# 13thISE_ver8.net
KiCad netlist of a schematic drawn in EAGLE
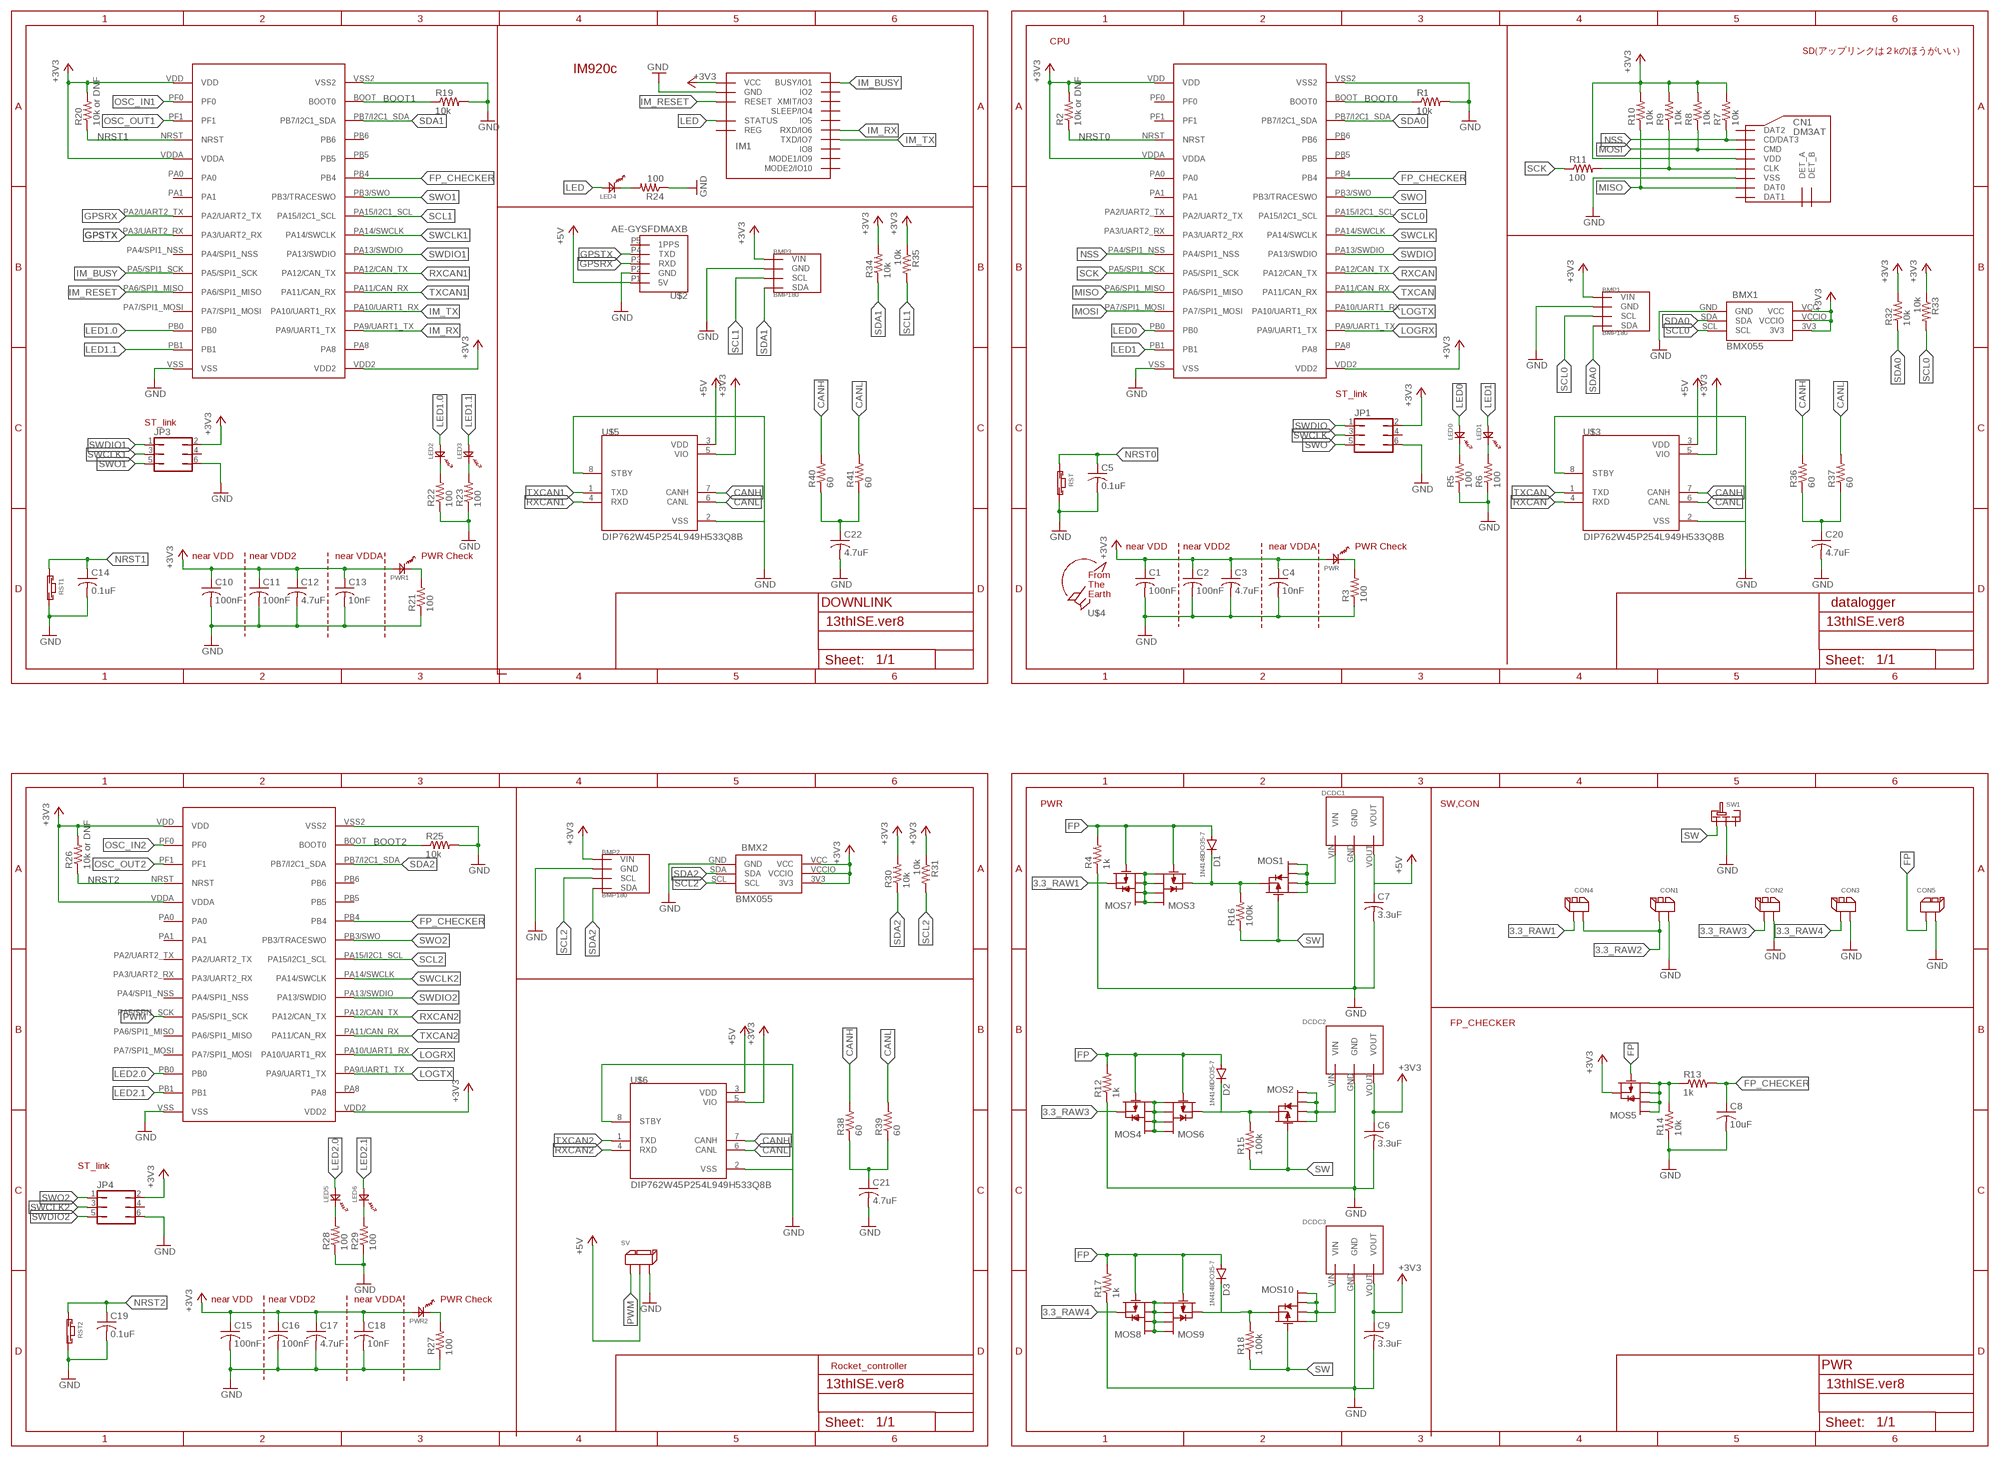
[diagram p0: schematic, sheet 1]

(export (version "E")
  (design (tool "Eeschema 10.0.6"))
  (components
    (comp (ref "BMP1")
      (value "BMP180")
      (footprint "eagle-import:GY-68")
      (libsource (lib "eagle-import") (part "BMP180"))
    )
    (comp (ref "BMP2")
      (value "BMP180")
      (footprint "eagle-import:GY-68")
      (libsource (lib "eagle-import") (part "BMP180"))
    )
    (comp (ref "BMP3")
      (value "BMP180")
      (footprint "eagle-import:GY-68")
      (libsource (lib "eagle-import") (part "BMP180"))
    )
    (comp (ref "BMX1")
      (value "BMX055")
      (footprint "eagle-import:BMX055")
      (libsource (lib "eagle-import") (part "BMX055"))
    )
    (comp (ref "BMX2")
      (value "BMX055")
      (footprint "eagle-import:BMX055")
      (libsource (lib "eagle-import") (part "BMX055"))
    )
    (comp (ref "C1")
      (value "100nF")
      (footprint "eagle-import:C1608")
      (libsource (lib "eagle-import") (part "C-USC1608"))
    )
    (comp (ref "C2")
      (value "100nF")
      (footprint "eagle-import:C1608")
      (libsource (lib "eagle-import") (part "C-USC1608"))
    )
    (comp (ref "C3")
      (value "4.7uF")
      (footprint "eagle-import:C1608")
      (libsource (lib "eagle-import") (part "C-USC1608"))
    )
    (comp (ref "C4")
      (value "10nF")
      (footprint "eagle-import:C1608")
      (libsource (lib "eagle-import") (part "C-USC1608"))
    )
    (comp (ref "C5")
      (value "0.1uF")
      (footprint "eagle-import:C1608")
      (libsource (lib "eagle-import") (part "C-USC1608"))
    )
    (comp (ref "C6")
      (value "3.3uF")
      (footprint "eagle-import:C0603")
      (libsource (lib "eagle-import") (part "C-USC0603"))
    )
    (comp (ref "C7")
      (value "3.3uF")
      (footprint "eagle-import:C0603")
      (libsource (lib "eagle-import") (part "C-USC0603"))
    )
    (comp (ref "C8")
      (value "10uF")
      (footprint "eagle-import:C0603")
      (libsource (lib "eagle-import") (part "C-USC0603"))
    )
    (comp (ref "C9")
      (value "3.3uF")
      (footprint "eagle-import:C0603")
      (libsource (lib "eagle-import") (part "C-USC0603"))
    )
    (comp (ref "C10")
      (value "100nF")
      (footprint "eagle-import:C1608")
      (libsource (lib "eagle-import") (part "C-USC1608"))
    )
    (comp (ref "C11")
      (value "100nF")
      (footprint "eagle-import:C1608")
      (libsource (lib "eagle-import") (part "C-USC1608"))
    )
    (comp (ref "C12")
      (value "4.7uF")
      (footprint "eagle-import:C1608")
      (libsource (lib "eagle-import") (part "C-USC1608"))
    )
    (comp (ref "C13")
      (value "10nF")
      (footprint "eagle-import:C1608")
      (libsource (lib "eagle-import") (part "C-USC1608"))
    )
    (comp (ref "C14")
      (value "0.1uF")
      (footprint "eagle-import:C1608")
      (libsource (lib "eagle-import") (part "C-USC1608"))
    )
    (comp (ref "C15")
      (value "100nF")
      (footprint "eagle-import:C1608")
      (libsource (lib "eagle-import") (part "C-USC1608"))
    )
    (comp (ref "C16")
      (value "100nF")
      (footprint "eagle-import:C1608")
      (libsource (lib "eagle-import") (part "C-USC1608"))
    )
    (comp (ref "C17")
      (value "4.7uF")
      (footprint "eagle-import:C1608")
      (libsource (lib "eagle-import") (part "C-USC1608"))
    )
    (comp (ref "C18")
      (value "10nF")
      (footprint "eagle-import:C1608")
      (libsource (lib "eagle-import") (part "C-USC1608"))
    )
    (comp (ref "C19")
      (value "0.1uF")
      (footprint "eagle-import:C1608")
      (libsource (lib "eagle-import") (part "C-USC1608"))
    )
    (comp (ref "C20")
      (value "4.7uF")
      (footprint "eagle-import:C0603")
      (libsource (lib "eagle-import") (part "C-USC0603"))
    )
    (comp (ref "C21")
      (value "4.7uF")
      (footprint "eagle-import:C0603")
      (libsource (lib "eagle-import") (part "C-USC0603"))
    )
    (comp (ref "C22")
      (value "4.7uF")
      (footprint "eagle-import:C0603")
      (libsource (lib "eagle-import") (part "C-USC0603"))
    )
    (comp (ref "CN1")
      (value "DM3AT")
      (footprint "eagle-import:DM3AT")
      (libsource (lib "eagle-import") (part "DM3AT"))
    )
    (comp (ref "CON1")
      (value "2PIN")
      (footprint "eagle-import:2PIN")
      (libsource (lib "eagle-import") (part "2PIN"))
    )
    (comp (ref "CON2")
      (value "2PIN")
      (footprint "eagle-import:2PIN")
      (libsource (lib "eagle-import") (part "2PIN"))
    )
    (comp (ref "CON3")
      (value "2PIN")
      (footprint "eagle-import:2PIN")
      (libsource (lib "eagle-import") (part "2PIN"))
    )
    (comp (ref "CON4")
      (value "2PIN")
      (footprint "eagle-import:2PIN")
      (libsource (lib "eagle-import") (part "2PIN"))
    )
    (comp (ref "CON5")
      (value "2PIN")
      (footprint "eagle-import:2PIN")
      (libsource (lib "eagle-import") (part "2PIN"))
    )
    (comp (ref "D1")
      (value "1N4148DO35-7")
      (footprint "eagle-import:DO35-7")
      (libsource (lib "eagle-import") (part "1N4148DO35-7"))
    )
    (comp (ref "D2")
      (value "1N4148DO35-7")
      (footprint "eagle-import:DO35-7")
      (libsource (lib "eagle-import") (part "1N4148DO35-7"))
    )
    (comp (ref "D3")
      (value "1N4148DO35-7")
      (footprint "eagle-import:DO35-7")
      (libsource (lib "eagle-import") (part "1N4148DO35-7"))
    )
    (comp (ref "DCDC1")
      (value "5V1A_M78AR05-1")
      (footprint "eagle-import:5V1A_M78AR05-1")
      (libsource (lib "eagle-import") (part "5V1A_M78AR05-1"))
    )
    (comp (ref "DCDC2")
      (value "3.3V1A_M78AR033-1")
      (footprint "eagle-import:3.3V1A_M78AR033-1")
      (libsource (lib "eagle-import") (part "3.3V1A_M78AR033-1"))
    )
    (comp (ref "DCDC3")
      (value "3.3V1A_M78AR033-1")
      (footprint "eagle-import:3.3V1A_M78AR033-1")
      (libsource (lib "eagle-import") (part "3.3V1A_M78AR033-1"))
    )
    (comp (ref "IM1")
      (value "IM920_IM920C")
      (footprint "eagle-import:IM920_IM920C")
      (libsource (lib "eagle-import") (part "IM920_IM920C"))
    )
    (comp (ref "JP1")
      (value "JP3Q")
      (footprint "eagle-import:JP3Q")
      (libsource (lib "eagle-import") (part "JP3Q"))
    )
    (comp (ref "JP3")
      (value "JP3Q")
      (footprint "eagle-import:JP3Q")
      (libsource (lib "eagle-import") (part "JP3Q"))
    )
    (comp (ref "JP4")
      (value "JP3Q")
      (footprint "eagle-import:JP3Q")
      (libsource (lib "eagle-import") (part "JP3Q"))
    )
    (comp (ref "LED0")
      (value "OSXX1608C1A")
      (footprint "eagle-import:OSXX1608C1A")
      (libsource (lib "eagle-import") (part "OSXX1608C1A"))
    )
    (comp (ref "LED1")
      (value "OSXX1608C1A")
      (footprint "eagle-import:OSXX1608C1A")
      (libsource (lib "eagle-import") (part "OSXX1608C1A"))
    )
    (comp (ref "LED2")
      (value "OSXX1608C1A")
      (footprint "eagle-import:OSXX1608C1A")
      (libsource (lib "eagle-import") (part "OSXX1608C1A"))
    )
    (comp (ref "LED3")
      (value "OSXX1608C1A")
      (footprint "eagle-import:OSXX1608C1A")
      (libsource (lib "eagle-import") (part "OSXX1608C1A"))
    )
    (comp (ref "LED4")
      (value "OSXX1608C1A")
      (footprint "eagle-import:OSXX1608C1A")
      (libsource (lib "eagle-import") (part "OSXX1608C1A"))
    )
    (comp (ref "LED5")
      (value "OSXX1608C1A")
      (footprint "eagle-import:OSXX1608C1A")
      (libsource (lib "eagle-import") (part "OSXX1608C1A"))
    )
    (comp (ref "LED6")
      (value "OSXX1608C1A")
      (footprint "eagle-import:OSXX1608C1A")
      (libsource (lib "eagle-import") (part "OSXX1608C1A"))
    )
    (comp (ref "MOS1")
      (value "PCH_SSM6J808R")
      (footprint "eagle-import:SSM6J808R")
      (libsource (lib "eagle-import") (part "PCH_SSM6J808R"))
    )
    (comp (ref "MOS2")
      (value "PCH_SSM6J808R")
      (footprint "eagle-import:SSM6J808R")
      (libsource (lib "eagle-import") (part "PCH_SSM6J808R"))
    )
    (comp (ref "MOS3")
      (value "PCH_SSM6J808R")
      (footprint "eagle-import:SSM6J808R")
      (libsource (lib "eagle-import") (part "PCH_SSM6J808R"))
    )
    (comp (ref "MOS4")
      (value "PCH_SSM6J808R")
      (footprint "eagle-import:SSM6J808R")
      (libsource (lib "eagle-import") (part "PCH_SSM6J808R"))
    )
    (comp (ref "MOS5")
      (value "PCH_SSM6J808R")
      (footprint "eagle-import:SSM6J808R")
      (libsource (lib "eagle-import") (part "PCH_SSM6J808R"))
    )
    (comp (ref "MOS6")
      (value "PCH_SSM6J808R")
      (footprint "eagle-import:SSM6J808R")
      (libsource (lib "eagle-import") (part "PCH_SSM6J808R"))
    )
    (comp (ref "MOS7")
      (value "PCH_SSM6J808R")
      (footprint "eagle-import:SSM6J808R")
      (libsource (lib "eagle-import") (part "PCH_SSM6J808R"))
    )
    (comp (ref "MOS8")
      (value "PCH_SSM6J808R")
      (footprint "eagle-import:SSM6J808R")
      (libsource (lib "eagle-import") (part "PCH_SSM6J808R"))
    )
    (comp (ref "MOS9")
      (value "PCH_SSM6J808R")
      (footprint "eagle-import:SSM6J808R")
      (libsource (lib "eagle-import") (part "PCH_SSM6J808R"))
    )
    (comp (ref "MOS10")
      (value "PCH_SSM6J808R")
      (footprint "eagle-import:SSM6J808R")
      (libsource (lib "eagle-import") (part "PCH_SSM6J808R"))
    )
    (comp (ref "PWR")
      (value "OSXX1608C1A")
      (footprint "eagle-import:OSXX1608C1A")
      (libsource (lib "eagle-import") (part "OSXX1608C1A"))
    )
    (comp (ref "PWR1")
      (value "OSXX1608C1A")
      (footprint "eagle-import:OSXX1608C1A")
      (libsource (lib "eagle-import") (part "OSXX1608C1A"))
    )
    (comp (ref "PWR2")
      (value "OSXX1608C1A")
      (footprint "eagle-import:OSXX1608C1A")
      (libsource (lib "eagle-import") (part "OSXX1608C1A"))
    )
    (comp (ref "R1")
      (value "10k")
      (footprint "eagle-import:R0603")
      (libsource (lib "eagle-import") (part "R-US_R0603"))
    )
    (comp (ref "R2")
      (value "10k or DNF")
      (footprint "eagle-import:R0603")
      (libsource (lib "eagle-import") (part "R-US_R0603"))
    )
    (comp (ref "R3")
      (value "100")
      (footprint "eagle-import:R0603")
      (libsource (lib "eagle-import") (part "R-US_R0603"))
    )
    (comp (ref "R4")
      (value "1k")
      (footprint "eagle-import:R0603")
      (libsource (lib "eagle-import") (part "R-US_R0603"))
    )
    (comp (ref "R5")
      (value "100")
      (footprint "eagle-import:R0603")
      (libsource (lib "eagle-import") (part "R-US_R0603"))
    )
    (comp (ref "R6")
      (value "100")
      (footprint "eagle-import:R0603")
      (libsource (lib "eagle-import") (part "R-US_R0603"))
    )
    (comp (ref "R7")
      (value "10k")
      (footprint "eagle-import:R0603")
      (libsource (lib "eagle-import") (part "R-US_R0603"))
    )
    (comp (ref "R8")
      (value "10k")
      (footprint "eagle-import:R0603")
      (libsource (lib "eagle-import") (part "R-US_R0603"))
    )
    (comp (ref "R9")
      (value "10k")
      (footprint "eagle-import:R0603")
      (libsource (lib "eagle-import") (part "R-US_R0603"))
    )
    (comp (ref "R10")
      (value "10k")
      (footprint "eagle-import:R0603")
      (libsource (lib "eagle-import") (part "R-US_R0603"))
    )
    (comp (ref "R11")
      (value "100")
      (footprint "eagle-import:R0603")
      (libsource (lib "eagle-import") (part "R-US_R0603"))
    )
    (comp (ref "R12")
      (value "1k")
      (footprint "eagle-import:R0603")
      (libsource (lib "eagle-import") (part "R-US_R0603"))
    )
    (comp (ref "R13")
      (value "1k")
      (footprint "eagle-import:R0603")
      (libsource (lib "eagle-import") (part "R-US_R0603"))
    )
    (comp (ref "R14")
      (value "10k")
      (footprint "eagle-import:R0603")
      (libsource (lib "eagle-import") (part "R-US_R0603"))
    )
    (comp (ref "R15")
      (value "100k")
      (footprint "eagle-import:R0603")
      (libsource (lib "eagle-import") (part "R-US_R0603"))
    )
    (comp (ref "R16")
      (value "100k")
      (footprint "eagle-import:R0603")
      (libsource (lib "eagle-import") (part "R-US_R0603"))
    )
    (comp (ref "R17")
      (value "1k")
      (footprint "eagle-import:R0603")
      (libsource (lib "eagle-import") (part "R-US_R0603"))
    )
    (comp (ref "R18")
      (value "100k")
      (footprint "eagle-import:R0603")
      (libsource (lib "eagle-import") (part "R-US_R0603"))
    )
    (comp (ref "R19")
      (value "10k")
      (footprint "eagle-import:R0603")
      (libsource (lib "eagle-import") (part "R-US_R0603"))
    )
    (comp (ref "R20")
      (value "10k or DNF")
      (footprint "eagle-import:R0603")
      (libsource (lib "eagle-import") (part "R-US_R0603"))
    )
    (comp (ref "R21")
      (value "100")
      (footprint "eagle-import:R0603")
      (libsource (lib "eagle-import") (part "R-US_R0603"))
    )
    (comp (ref "R22")
      (value "100")
      (footprint "eagle-import:R0603")
      (libsource (lib "eagle-import") (part "R-US_R0603"))
    )
    (comp (ref "R23")
      (value "100")
      (footprint "eagle-import:R0603")
      (libsource (lib "eagle-import") (part "R-US_R0603"))
    )
    (comp (ref "R24")
      (value "100")
      (footprint "eagle-import:R0603")
      (libsource (lib "eagle-import") (part "R-US_R0603"))
    )
    (comp (ref "R25")
      (value "10k")
      (footprint "eagle-import:R0603")
      (libsource (lib "eagle-import") (part "R-US_R0603"))
    )
    (comp (ref "R26")
      (value "10k or DNF")
      (footprint "eagle-import:R0603")
      (libsource (lib "eagle-import") (part "R-US_R0603"))
    )
    (comp (ref "R27")
      (value "100")
      (footprint "eagle-import:R0603")
      (libsource (lib "eagle-import") (part "R-US_R0603"))
    )
    (comp (ref "R28")
      (value "100")
      (footprint "eagle-import:R0603")
      (libsource (lib "eagle-import") (part "R-US_R0603"))
    )
    (comp (ref "R29")
      (value "100")
      (footprint "eagle-import:R0603")
      (libsource (lib "eagle-import") (part "R-US_R0603"))
    )
    (comp (ref "R30")
      (value "10k")
      (footprint "eagle-import:R0603")
      (libsource (lib "eagle-import") (part "R-US_R0603"))
    )
    (comp (ref "R31")
      (value "10k")
      (footprint "eagle-import:R0603")
      (libsource (lib "eagle-import") (part "R-US_R0603"))
    )
    (comp (ref "R32")
      (value "10k")
      (footprint "eagle-import:R0603")
      (libsource (lib "eagle-import") (part "R-US_R0603"))
    )
    (comp (ref "R33")
      (value "10k")
      (footprint "eagle-import:R0603")
      (libsource (lib "eagle-import") (part "R-US_R0603"))
    )
    (comp (ref "R34")
      (value "10k")
      (footprint "eagle-import:R0603")
      (libsource (lib "eagle-import") (part "R-US_R0603"))
    )
    (comp (ref "R35")
      (value "10k")
      (footprint "eagle-import:R0603")
      (libsource (lib "eagle-import") (part "R-US_R0603"))
    )
    (comp (ref "R36")
      (value "60")
      (footprint "eagle-import:R0603")
      (libsource (lib "eagle-import") (part "R-US_R0603"))
    )
    (comp (ref "R37")
      (value "60")
      (footprint "eagle-import:R0603")
      (libsource (lib "eagle-import") (part "R-US_R0603"))
    )
    (comp (ref "R38")
      (value "60")
      (footprint "eagle-import:R0603")
      (libsource (lib "eagle-import") (part "R-US_R0603"))
    )
    (comp (ref "R39")
      (value "60")
      (footprint "eagle-import:R0603")
      (libsource (lib "eagle-import") (part "R-US_R0603"))
    )
    (comp (ref "R40")
      (value "60")
      (footprint "eagle-import:R0603")
      (libsource (lib "eagle-import") (part "R-US_R0603"))
    )
    (comp (ref "R41")
      (value "60")
      (footprint "eagle-import:R0603")
      (libsource (lib "eagle-import") (part "R-US_R0603"))
    )
    (comp (ref "RST")
      (value "TVAF06-A020B-R")
      (footprint "eagle-import:TVAF06-A020B-R")
      (libsource (lib "eagle-import") (part "TVAF06-A020B-R"))
    )
    (comp (ref "RST1")
      (value "TVAF06-A020B-R")
      (footprint "eagle-import:TVAF06-A020B-R")
      (libsource (lib "eagle-import") (part "TVAF06-A020B-R"))
    )
    (comp (ref "RST2")
      (value "TVAF06-A020B-R")
      (footprint "eagle-import:TVAF06-A020B-R")
      (libsource (lib "eagle-import") (part "TVAF06-A020B-R"))
    )
    (comp (ref "STM0")
      (value "STM32F303K8")
      (footprint "eagle-import:STM32F303K8")
      (libsource (lib "eagle-import") (part "STM32F303K8"))
    )
    (comp (ref "STM1")
      (value "STM32F303K8")
      (footprint "eagle-import:STM32F303K8")
      (libsource (lib "eagle-import") (part "STM32F303K8"))
    )
    (comp (ref "SV")
      (value "3PIN")
      (footprint "eagle-import:3PIN")
      (libsource (lib "eagle-import") (part "3PIN"))
    )
    (comp (ref "SW1")
      (value "SRIDE_SWITCH")
      (footprint "eagle-import:SRIDE_SWITCH")
      (libsource (lib "eagle-import") (part "SRIDE_SWITCH"))
    )
    (comp (ref "U$1")
      (value "STM32F303K8")
      (footprint "eagle-import:STM32F303K8")
      (libsource (lib "eagle-import") (part "STM32F303K8"))
    )
    (comp (ref "U$2")
      (value "AE-GYSFDMAXB")
      (footprint "eagle-import:AE-GYSFDMAXB")
      (libsource (lib "eagle-import") (part "AE-GYSFDMAXB"))
    )
    (comp (ref "U$3")
      (value "DIP762W45P254L949H533Q8B")
      (footprint "eagle-import:DIP762W45P254L949H533Q8B")
      (libsource (lib "eagle-import") (part "DIP762W45P254L949H533Q8B"))
    )
    (comp (ref "U$4")
      (value "F.T.E.LOGO")
      (footprint "eagle-import:LOGO")
      (libsource (lib "eagle-import") (part "F.T.E.LOGO"))
    )
    (comp (ref "U$5")
      (value "DIP762W45P254L949H533Q8B")
      (footprint "eagle-import:DIP762W45P254L949H533Q8B")
      (libsource (lib "eagle-import") (part "DIP762W45P254L949H533Q8B"))
    )
    (comp (ref "U$6")
      (value "DIP762W45P254L949H533Q8B")
      (footprint "eagle-import:DIP762W45P254L949H533Q8B")
      (libsource (lib "eagle-import") (part "DIP762W45P254L949H533Q8B"))
    )
  )
  (nets
    (net (code "1") (name "+3V3") (class "Default")
      (node (ref "BMP1") (pin "P1") (pinfunction "VIN_P1") (pintype "bidirectional"))
      (node (ref "BMP2") (pin "P1") (pinfunction "VIN_P1") (pintype "bidirectional"))
      (node (ref "BMP3") (pin "P1") (pinfunction "VIN_P1") (pintype "bidirectional"))
      (node (ref "BMX1") (pin "3V3") (pinfunction "3V3_3V3") (pintype "power_in"))
      (node (ref "BMX1") (pin "VCC") (pinfunction "VCC_VCC") (pintype "power_in"))
      (node (ref "BMX1") (pin "VCCIO") (pinfunction "VCCIO_VCCIO") (pintype "power_in"))
      (node (ref "BMX2") (pin "3V3") (pinfunction "3V3_3V3") (pintype "power_in"))
      (node (ref "BMX2") (pin "VCC") (pinfunction "VCC_VCC") (pintype "power_in"))
      (node (ref "BMX2") (pin "VCCIO") (pinfunction "VCCIO_VCCIO") (pintype "power_in"))
      (node (ref "C1") (pin "1") (pinfunction "1_1") (pintype "passive"))
      (node (ref "C10") (pin "1") (pinfunction "1_1") (pintype "passive"))
      (node (ref "C11") (pin "1") (pinfunction "1_1") (pintype "passive"))
      (node (ref "C12") (pin "1") (pinfunction "1_1") (pintype "passive"))
      (node (ref "C13") (pin "1") (pinfunction "1_1") (pintype "passive"))
      (node (ref "C15") (pin "1") (pinfunction "1_1") (pintype "passive"))
      (node (ref "C16") (pin "1") (pinfunction "1_1") (pintype "passive"))
      (node (ref "C17") (pin "1") (pinfunction "1_1") (pintype "passive"))
      (node (ref "C18") (pin "1") (pinfunction "1_1") (pintype "passive"))
      (node (ref "C2") (pin "1") (pinfunction "1_1") (pintype "passive"))
      (node (ref "C3") (pin "1") (pinfunction "1_1") (pintype "passive"))
      (node (ref "C4") (pin "1") (pinfunction "1_1") (pintype "passive"))
      (node (ref "C6") (pin "1") (pinfunction "1_1") (pintype "passive"))
      (node (ref "C9") (pin "1") (pinfunction "1_1") (pintype "passive"))
      (node (ref "CN1") (pin "VDD") (pinfunction "VDD_VDD") (pintype "bidirectional"))
      (node (ref "DCDC2") (pin "VOUT") (pinfunction "VOUT_VOUT") (pintype "bidirectional"))
      (node (ref "DCDC3") (pin "VOUT") (pinfunction "VOUT_VOUT") (pintype "bidirectional"))
      (node (ref "IM1") (pin "$P17") (pinfunction "VCC_$P17") (pintype "bidirectional"))
      (node (ref "JP1") (pin "2") (pinfunction "2_2") (pintype "passive"))
      (node (ref "JP3") (pin "2") (pinfunction "2_2") (pintype "passive"))
      (node (ref "JP4") (pin "2") (pinfunction "2_2") (pintype "passive"))
      (node (ref "MOS5") (pin "4") (pinfunction "4_4") (pintype "bidirectional"))
      (node (ref "PWR") (pin "AN") (pinfunction "AN_AN") (pintype "bidirectional"))
      (node (ref "PWR1") (pin "AN") (pinfunction "AN_AN") (pintype "bidirectional"))
      (node (ref "PWR2") (pin "AN") (pinfunction "AN_AN") (pintype "bidirectional"))
      (node (ref "R10") (pin "2") (pinfunction "2_2") (pintype "passive"))
      (node (ref "R2") (pin "2") (pinfunction "2_2") (pintype "passive"))
      (node (ref "R20") (pin "2") (pinfunction "2_2") (pintype "passive"))
      (node (ref "R26") (pin "2") (pinfunction "2_2") (pintype "passive"))
      (node (ref "R30") (pin "2") (pinfunction "2_2") (pintype "passive"))
      (node (ref "R31") (pin "1") (pinfunction "1_1") (pintype "passive"))
      (node (ref "R32") (pin "2") (pinfunction "2_2") (pintype "passive"))
      (node (ref "R33") (pin "1") (pinfunction "1_1") (pintype "passive"))
      (node (ref "R34") (pin "2") (pinfunction "2_2") (pintype "passive"))
      (node (ref "R35") (pin "1") (pinfunction "1_1") (pintype "passive"))
      (node (ref "R7") (pin "2") (pinfunction "2_2") (pintype "passive"))
      (node (ref "R8") (pin "2") (pinfunction "2_2") (pintype "passive"))
      (node (ref "R9") (pin "2") (pinfunction "2_2") (pintype "passive"))
      (node (ref "STM0") (pin "VDD") (pinfunction "VDD_VDD") (pintype "power_in"))
      (node (ref "STM0") (pin "VDD2") (pinfunction "VDD2_VDD2") (pintype "power_in"))
      (node (ref "STM0") (pin "VDDA") (pinfunction "VDDA_VDDA") (pintype "power_in"))
      (node (ref "STM1") (pin "VDD") (pinfunction "VDD_VDD") (pintype "power_in"))
      (node (ref "STM1") (pin "VDD2") (pinfunction "VDD2_VDD2") (pintype "power_in"))
      (node (ref "STM1") (pin "VDDA") (pinfunction "VDDA_VDDA") (pintype "power_in"))
      (node (ref "U$1") (pin "VDD") (pinfunction "VDD_VDD") (pintype "power_in"))
      (node (ref "U$1") (pin "VDD2") (pinfunction "VDD2_VDD2") (pintype "power_in"))
      (node (ref "U$1") (pin "VDDA") (pinfunction "VDDA_VDDA") (pintype "power_in"))
      (node (ref "U$3") (pin "5") (pinfunction "VIO_5") (pintype "power_in"))
      (node (ref "U$5") (pin "5") (pinfunction "VIO_5") (pintype "power_in"))
      (node (ref "U$6") (pin "5") (pinfunction "VIO_5") (pintype "power_in"))
    )
    (net (code "2") (name "+5V") (class "Default")
      (node (ref "C7") (pin "1") (pinfunction "1_1") (pintype "passive"))
      (node (ref "DCDC1") (pin "VOUT") (pinfunction "VOUT_VOUT") (pintype "bidirectional"))
      (node (ref "SV") (pin "P$2") (pinfunction "P$2_P$2") (pintype "bidirectional"))
      (node (ref "U$2") (pin "P1") (pinfunction "5V_P1") (pintype "bidirectional"))
      (node (ref "U$3") (pin "3") (pinfunction "VDD_3") (pintype "power_in"))
      (node (ref "U$5") (pin "3") (pinfunction "VDD_3") (pintype "power_in"))
      (node (ref "U$6") (pin "3") (pinfunction "VDD_3") (pintype "power_in"))
    )
    (net (code "3") (name "/BOOT0") (class "Default")
      (node (ref "R1") (pin "1") (pinfunction "1_1") (pintype "passive"))
      (node (ref "STM0") (pin "BOOT") (pinfunction "BOOT0_BOOT") (pintype "bidirectional"))
    )
    (net (code "4") (name "/BOOT1") (class "Default")
      (node (ref "R19") (pin "1") (pinfunction "1_1") (pintype "passive"))
      (node (ref "STM1") (pin "BOOT") (pinfunction "BOOT0_BOOT") (pintype "bidirectional"))
    )
    (net (code "5") (name "/BOOT2") (class "Default")
      (node (ref "R25") (pin "1") (pinfunction "1_1") (pintype "passive"))
      (node (ref "U$1") (pin "BOOT") (pinfunction "BOOT0_BOOT") (pintype "bidirectional"))
    )
    (net (code "6") (name "3.3_RAW1") (class "Default")
      (node (ref "CON4") (pin "P$2") (pinfunction "P$2_P$2") (pintype "bidirectional"))
      (node (ref "MOS7") (pin "4") (pinfunction "4_4") (pintype "bidirectional"))
    )
    (net (code "7") (name "3.3_RAW2") (class "Default")
      (node (ref "CON1") (pin "P$2") (pinfunction "P$2_P$2") (pintype "bidirectional"))
      (node (ref "CON4") (pin "P$1") (pinfunction "P$1_P$1") (pintype "bidirectional"))
    )
    (net (code "8") (name "3.3_RAW3") (class "Default")
      (node (ref "CON2") (pin "P$2") (pinfunction "P$2_P$2") (pintype "bidirectional"))
      (node (ref "MOS4") (pin "4") (pinfunction "4_4") (pintype "bidirectional"))
    )
    (net (code "9") (name "3.3_RAW4") (class "Default")
      (node (ref "CON3") (pin "P$2") (pinfunction "P$2_P$2") (pintype "bidirectional"))
      (node (ref "MOS8") (pin "4") (pinfunction "4_4") (pintype "bidirectional"))
    )
    (net (code "10") (name "CANH") (class "Default")
      (node (ref "R36") (pin "2") (pinfunction "2_2") (pintype "passive"))
      (node (ref "R38") (pin "2") (pinfunction "2_2") (pintype "passive"))
      (node (ref "R40") (pin "2") (pinfunction "2_2") (pintype "passive"))
      (node (ref "U$3") (pin "7") (pinfunction "CANH_7") (pintype "bidirectional"))
      (node (ref "U$5") (pin "7") (pinfunction "CANH_7") (pintype "bidirectional"))
      (node (ref "U$6") (pin "7") (pinfunction "CANH_7") (pintype "bidirectional"))
    )
    (net (code "11") (name "CANL") (class "Default")
      (node (ref "R37") (pin "2") (pinfunction "2_2") (pintype "passive"))
      (node (ref "R39") (pin "2") (pinfunction "2_2") (pintype "passive"))
      (node (ref "R41") (pin "2") (pinfunction "2_2") (pintype "passive"))
      (node (ref "U$3") (pin "6") (pinfunction "CANL_6") (pintype "bidirectional"))
      (node (ref "U$5") (pin "6") (pinfunction "CANL_6") (pintype "bidirectional"))
      (node (ref "U$6") (pin "6") (pinfunction "CANL_6") (pintype "bidirectional"))
    )
    (net (code "12") (name "FP") (class "Default")
      (node (ref "CON5") (pin "P$1") (pinfunction "P$1_P$1") (pintype "bidirectional"))
      (node (ref "D1") (pin "A") (pinfunction "A_A") (pintype "passive"))
      (node (ref "D2") (pin "A") (pinfunction "A_A") (pintype "passive"))
      (node (ref "D3") (pin "A") (pinfunction "A_A") (pintype "passive"))
      (node (ref "MOS3") (pin "3") (pinfunction "3_3") (pintype "bidirectional"))
      (node (ref "MOS4") (pin "3") (pinfunction "3_3") (pintype "bidirectional"))
      (node (ref "MOS5") (pin "3") (pinfunction "3_3") (pintype "bidirectional"))
      (node (ref "MOS6") (pin "3") (pinfunction "3_3") (pintype "bidirectional"))
      (node (ref "MOS7") (pin "3") (pinfunction "3_3") (pintype "bidirectional"))
      (node (ref "MOS8") (pin "3") (pinfunction "3_3") (pintype "bidirectional"))
      (node (ref "MOS9") (pin "3") (pinfunction "3_3") (pintype "bidirectional"))
      (node (ref "R12") (pin "2") (pinfunction "2_2") (pintype "passive"))
      (node (ref "R17") (pin "2") (pinfunction "2_2") (pintype "passive"))
      (node (ref "R4") (pin "2") (pinfunction "2_2") (pintype "passive"))
    )
    (net (code "13") (name "FP_CHECKER") (class "Default")
      (node (ref "C8") (pin "1") (pinfunction "1_1") (pintype "passive"))
      (node (ref "R13") (pin "2") (pinfunction "2_2") (pintype "passive"))
      (node (ref "STM0") (pin "PB4") (pinfunction "PB4_PB4") (pintype "bidirectional"))
      (node (ref "STM1") (pin "PB4") (pinfunction "PB4_PB4") (pintype "bidirectional"))
      (node (ref "U$1") (pin "PB4") (pinfunction "PB4_PB4") (pintype "bidirectional"))
    )
    (net (code "14") (name "GND") (class "Default")
      (node (ref "BMP1") (pin "P2") (pinfunction "GND_P2") (pintype "bidirectional"))
      (node (ref "BMP2") (pin "P2") (pinfunction "GND_P2") (pintype "bidirectional"))
      (node (ref "BMP3") (pin "P2") (pinfunction "GND_P2") (pintype "bidirectional"))
      (node (ref "BMX1") (pin "GND") (pinfunction "GND_GND") (pintype "power_in"))
      (node (ref "BMX2") (pin "GND") (pinfunction "GND_GND") (pintype "power_in"))
      (node (ref "C1") (pin "2") (pinfunction "2_2") (pintype "passive"))
      (node (ref "C10") (pin "2") (pinfunction "2_2") (pintype "passive"))
      (node (ref "C11") (pin "2") (pinfunction "2_2") (pintype "passive"))
      (node (ref "C12") (pin "2") (pinfunction "2_2") (pintype "passive"))
      (node (ref "C13") (pin "2") (pinfunction "2_2") (pintype "passive"))
      (node (ref "C14") (pin "2") (pinfunction "2_2") (pintype "passive"))
      (node (ref "C15") (pin "2") (pinfunction "2_2") (pintype "passive"))
      (node (ref "C16") (pin "2") (pinfunction "2_2") (pintype "passive"))
      (node (ref "C17") (pin "2") (pinfunction "2_2") (pintype "passive"))
      (node (ref "C18") (pin "2") (pinfunction "2_2") (pintype "passive"))
      (node (ref "C19") (pin "2") (pinfunction "2_2") (pintype "passive"))
      (node (ref "C2") (pin "2") (pinfunction "2_2") (pintype "passive"))
      (node (ref "C20") (pin "2") (pinfunction "2_2") (pintype "passive"))
      (node (ref "C21") (pin "2") (pinfunction "2_2") (pintype "passive"))
      (node (ref "C22") (pin "2") (pinfunction "2_2") (pintype "passive"))
      (node (ref "C3") (pin "2") (pinfunction "2_2") (pintype "passive"))
      (node (ref "C4") (pin "2") (pinfunction "2_2") (pintype "passive"))
      (node (ref "C5") (pin "2") (pinfunction "2_2") (pintype "passive"))
      (node (ref "C6") (pin "2") (pinfunction "2_2") (pintype "passive"))
      (node (ref "C7") (pin "2") (pinfunction "2_2") (pintype "passive"))
      (node (ref "C8") (pin "2") (pinfunction "2_2") (pintype "passive"))
      (node (ref "C9") (pin "2") (pinfunction "2_2") (pintype "passive"))
      (node (ref "CN1") (pin "VSS") (pinfunction "VSS_VSS") (pintype "bidirectional"))
      (node (ref "CON1") (pin "P$1") (pinfunction "P$1_P$1") (pintype "bidirectional"))
      (node (ref "CON2") (pin "P$1") (pinfunction "P$1_P$1") (pintype "bidirectional"))
      (node (ref "CON3") (pin "P$1") (pinfunction "P$1_P$1") (pintype "bidirectional"))
      (node (ref "CON5") (pin "P$2") (pinfunction "P$2_P$2") (pintype "bidirectional"))
      (node (ref "DCDC1") (pin "GND") (pinfunction "GND_GND") (pintype "bidirectional"))
      (node (ref "DCDC2") (pin "GND") (pinfunction "GND_GND") (pintype "bidirectional"))
      (node (ref "DCDC3") (pin "GND") (pinfunction "GND_GND") (pintype "bidirectional"))
      (node (ref "IM1") (pin "$P18") (pinfunction "GND_$P18") (pintype "bidirectional"))
      (node (ref "JP1") (pin "6") (pinfunction "6_6") (pintype "passive"))
      (node (ref "JP3") (pin "6") (pinfunction "6_6") (pintype "passive"))
      (node (ref "JP4") (pin "6") (pinfunction "6_6") (pintype "passive"))
      (node (ref "R1") (pin "2") (pinfunction "2_2") (pintype "passive"))
      (node (ref "R12") (pin "1") (pinfunction "1_1") (pintype "passive"))
      (node (ref "R14") (pin "1") (pinfunction "1_1") (pintype "passive"))
      (node (ref "R17") (pin "1") (pinfunction "1_1") (pintype "passive"))
      (node (ref "R19") (pin "2") (pinfunction "2_2") (pintype "passive"))
      (node (ref "R21") (pin "1") (pinfunction "1_1") (pintype "passive"))
      (node (ref "R22") (pin "1") (pinfunction "1_1") (pintype "passive"))
      (node (ref "R23") (pin "1") (pinfunction "1_1") (pintype "passive"))
      (node (ref "R24") (pin "1") (pinfunction "1_1") (pintype "passive"))
      (node (ref "R25") (pin "2") (pinfunction "2_2") (pintype "passive"))
      (node (ref "R27") (pin "1") (pinfunction "1_1") (pintype "passive"))
      (node (ref "R28") (pin "1") (pinfunction "1_1") (pintype "passive"))
      (node (ref "R29") (pin "1") (pinfunction "1_1") (pintype "passive"))
      (node (ref "R3") (pin "1") (pinfunction "1_1") (pintype "passive"))
      (node (ref "R4") (pin "1") (pinfunction "1_1") (pintype "passive"))
      (node (ref "R5") (pin "1") (pinfunction "1_1") (pintype "passive"))
      (node (ref "R6") (pin "1") (pinfunction "1_1") (pintype "passive"))
      (node (ref "RST") (pin "P$2") (pinfunction "P$2_P$2") (pintype "bidirectional"))
      (node (ref "RST1") (pin "P$2") (pinfunction "P$2_P$2") (pintype "bidirectional"))
      (node (ref "RST2") (pin "P$2") (pinfunction "P$2_P$2") (pintype "bidirectional"))
      (node (ref "STM0") (pin "VSS") (pinfunction "VSS_VSS") (pintype "power_in"))
      (node (ref "STM0") (pin "VSS2") (pinfunction "VSS2_VSS2") (pintype "power_in"))
      (node (ref "STM1") (pin "VSS") (pinfunction "VSS_VSS") (pintype "power_in"))
      (node (ref "STM1") (pin "VSS2") (pinfunction "VSS2_VSS2") (pintype "power_in"))
      (node (ref "SV") (pin "P$3") (pinfunction "P$3_P$3") (pintype "bidirectional"))
      (node (ref "SW1") (pin "LR") (pinfunction "LR_LR") (pintype "bidirectional"))
      (node (ref "U$1") (pin "VSS") (pinfunction "VSS_VSS") (pintype "power_in"))
      (node (ref "U$1") (pin "VSS2") (pinfunction "VSS2_VSS2") (pintype "power_in"))
      (node (ref "U$2") (pin "P2") (pinfunction "GND_P2") (pintype "bidirectional"))
      (node (ref "U$3") (pin "2") (pinfunction "VSS_2") (pintype "power_in"))
      (node (ref "U$3") (pin "8") (pinfunction "STBY_8") (pintype "input"))
      (node (ref "U$5") (pin "2") (pinfunction "VSS_2") (pintype "power_in"))
      (node (ref "U$5") (pin "8") (pinfunction "STBY_8") (pintype "input"))
      (node (ref "U$6") (pin "2") (pinfunction "VSS_2") (pintype "power_in"))
      (node (ref "U$6") (pin "8") (pinfunction "STBY_8") (pintype "input"))
    )
    (net (code "15") (name "GPSRX") (class "Default")
      (node (ref "STM1") (pin "PA2/UART2_TX") (pinfunction "PA2/UART2_TX_PA2/UART2_TX") (pintype "bidirectional"))
      (node (ref "U$2") (pin "P3") (pinfunction "RXD_P3") (pintype "bidirectional"))
    )
    (net (code "16") (name "GPSTX") (class "Default")
      (node (ref "STM1") (pin "PA3/UART2_RX") (pinfunction "PA3/UART2_RX_PA3/UART2_RX") (pintype "bidirectional"))
      (node (ref "U$2") (pin "P4") (pinfunction "TXD_P4") (pintype "bidirectional"))
    )
    (net (code "17") (name "IM_BUSY") (class "Default")
      (node (ref "IM1") (pin "$P1") (pinfunction "BUSY/IO1_$P1") (pintype "bidirectional"))
      (node (ref "STM1") (pin "PA5/SPI1_SCK") (pinfunction "PA5/SPI1_SCK_PA5/SPI1_SCK") (pintype "bidirectional"))
    )
    (net (code "18") (name "IM_RESET") (class "Default")
      (node (ref "IM1") (pin "$P19") (pinfunction "RESET_$P19") (pintype "bidirectional"))
      (node (ref "STM1") (pin "PA6/SPI1_MISO") (pinfunction "PA6/SPI1_MISO_PA6/SPI1_MISO") (pintype "bidirectional"))
    )
    (net (code "19") (name "IM_RX") (class "Default")
      (node (ref "IM1") (pin "$P6") (pinfunction "RXD/IO6_$P6") (pintype "bidirectional"))
      (node (ref "STM1") (pin "PA9/UART1_TX") (pinfunction "PA9/UART1_TX_PA9/UART1_TX") (pintype "bidirectional"))
    )
    (net (code "20") (name "IM_TX") (class "Default")
      (node (ref "IM1") (pin "$P7") (pinfunction "TXD/IO7_$P7") (pintype "bidirectional"))
      (node (ref "STM1") (pin "PA10/UART1_RX") (pinfunction "PA10/UART1_RX_PA10/UART1_RX") (pintype "bidirectional"))
    )
    (net (code "21") (name "LED") (class "Default")
      (node (ref "IM1") (pin "$P15") (pinfunction "STATUS_$P15") (pintype "bidirectional"))
      (node (ref "LED4") (pin "AN") (pinfunction "AN_AN") (pintype "bidirectional"))
    )
    (net (code "22") (name "LED0") (class "Default")
      (node (ref "LED0") (pin "AN") (pinfunction "AN_AN") (pintype "bidirectional"))
      (node (ref "STM0") (pin "PB0") (pinfunction "PB0_PB0") (pintype "bidirectional"))
    )
    (net (code "23") (name "LED1") (class "Default")
      (node (ref "LED1") (pin "AN") (pinfunction "AN_AN") (pintype "bidirectional"))
      (node (ref "STM0") (pin "PB1") (pinfunction "PB1_PB1") (pintype "bidirectional"))
    )
    (net (code "24") (name "LED1.0") (class "Default")
      (node (ref "LED2") (pin "AN") (pinfunction "AN_AN") (pintype "bidirectional"))
      (node (ref "STM1") (pin "PB0") (pinfunction "PB0_PB0") (pintype "bidirectional"))
    )
    (net (code "25") (name "LED1.1") (class "Default")
      (node (ref "LED3") (pin "AN") (pinfunction "AN_AN") (pintype "bidirectional"))
      (node (ref "STM1") (pin "PB1") (pinfunction "PB1_PB1") (pintype "bidirectional"))
    )
    (net (code "26") (name "LED2.0") (class "Default")
      (node (ref "LED5") (pin "AN") (pinfunction "AN_AN") (pintype "bidirectional"))
      (node (ref "U$1") (pin "PB0") (pinfunction "PB0_PB0") (pintype "bidirectional"))
    )
    (net (code "27") (name "LED2.1") (class "Default")
      (node (ref "LED6") (pin "AN") (pinfunction "AN_AN") (pintype "bidirectional"))
      (node (ref "U$1") (pin "PB1") (pinfunction "PB1_PB1") (pintype "bidirectional"))
    )
    (net (code "28") (name "LOGRX") (class "Default")
      (node (ref "STM0") (pin "PA9/UART1_TX") (pinfunction "PA9/UART1_TX_PA9/UART1_TX") (pintype "bidirectional"))
      (node (ref "U$1") (pin "PA10/UART1_RX") (pinfunction "PA10/UART1_RX_PA10/UART1_RX") (pintype "bidirectional"))
    )
    (net (code "29") (name "LOGTX") (class "Default")
      (node (ref "STM0") (pin "PA10/UART1_RX") (pinfunction "PA10/UART1_RX_PA10/UART1_RX") (pintype "bidirectional"))
      (node (ref "U$1") (pin "PA9/UART1_TX") (pinfunction "PA9/UART1_TX_PA9/UART1_TX") (pintype "bidirectional"))
    )
    (net (code "30") (name "MISO") (class "Default")
      (node (ref "CN1") (pin "DAT0") (pinfunction "DAT0_DAT0") (pintype "bidirectional"))
      (node (ref "R10") (pin "1") (pinfunction "1_1") (pintype "passive"))
      (node (ref "STM0") (pin "PA6/SPI1_MISO") (pinfunction "PA6/SPI1_MISO_PA6/SPI1_MISO") (pintype "bidirectional"))
    )
    (net (code "31") (name "MOSI") (class "Default")
      (node (ref "CN1") (pin "CMD") (pinfunction "CMD_CMD") (pintype "bidirectional"))
      (node (ref "R8") (pin "1") (pinfunction "1_1") (pintype "passive"))
      (node (ref "STM0") (pin "PA7/SPI1_MOSI") (pinfunction "PA7/SPI1_MOSI_PA7/SPI1_MOSI") (pintype "bidirectional"))
    )
    (net (code "32") (name "NRST0") (class "Default")
      (node (ref "C5") (pin "1") (pinfunction "1_1") (pintype "passive"))
      (node (ref "R2") (pin "1") (pinfunction "1_1") (pintype "passive"))
      (node (ref "RST") (pin "P$1") (pinfunction "P$1_P$1") (pintype "bidirectional"))
      (node (ref "STM0") (pin "NRST") (pinfunction "NRST_NRST") (pintype "bidirectional"))
    )
    (net (code "33") (name "NRST1") (class "Default")
      (node (ref "C14") (pin "1") (pinfunction "1_1") (pintype "passive"))
      (node (ref "R20") (pin "1") (pinfunction "1_1") (pintype "passive"))
      (node (ref "RST1") (pin "P$1") (pinfunction "P$1_P$1") (pintype "bidirectional"))
      (node (ref "STM1") (pin "NRST") (pinfunction "NRST_NRST") (pintype "bidirectional"))
    )
    (net (code "34") (name "NRST2") (class "Default")
      (node (ref "C19") (pin "1") (pinfunction "1_1") (pintype "passive"))
      (node (ref "R26") (pin "1") (pinfunction "1_1") (pintype "passive"))
      (node (ref "RST2") (pin "P$1") (pinfunction "P$1_P$1") (pintype "bidirectional"))
      (node (ref "U$1") (pin "NRST") (pinfunction "NRST_NRST") (pintype "bidirectional"))
    )
    (net (code "35") (name "NSS") (class "Default")
      (node (ref "CN1") (pin "CD/DAT3") (pinfunction "CD/DAT3_CD/DAT3") (pintype "bidirectional"))
      (node (ref "R7") (pin "1") (pinfunction "1_1") (pintype "passive"))
      (node (ref "STM0") (pin "PA4/SPI1_NSS") (pinfunction "PA4/SPI1_NSS_PA4/SPI1_NSS") (pintype "bidirectional"))
    )
    (net (code "36") (name "Net-(C20-Pad1)") (class "Default")
      (node (ref "C20") (pin "1") (pinfunction "1_1") (pintype "passive"))
      (node (ref "R36") (pin "1") (pinfunction "1_1") (pintype "passive"))
      (node (ref "R37") (pin "1") (pinfunction "1_1") (pintype "passive"))
    )
    (net (code "37") (name "Net-(C21-Pad1)") (class "Default")
      (node (ref "C21") (pin "1") (pinfunction "1_1") (pintype "passive"))
      (node (ref "R38") (pin "1") (pinfunction "1_1") (pintype "passive"))
      (node (ref "R39") (pin "1") (pinfunction "1_1") (pintype "passive"))
    )
    (net (code "38") (name "Net-(C22-Pad1)") (class "Default")
      (node (ref "C22") (pin "1") (pinfunction "1_1") (pintype "passive"))
      (node (ref "R40") (pin "1") (pinfunction "1_1") (pintype "passive"))
      (node (ref "R41") (pin "1") (pinfunction "1_1") (pintype "passive"))
    )
    (net (code "39") (name "Net-(CN1-PadCLK)") (class "Default")
      (node (ref "CN1") (pin "CLK") (pinfunction "CLK_CLK") (pintype "bidirectional"))
      (node (ref "R11") (pin "2") (pinfunction "2_2") (pintype "passive"))
      (node (ref "R9") (pin "1") (pinfunction "1_1") (pintype "passive"))
    )
    (net (code "40") (name "Net-(D1-PadC)") (class "Default")
      (node (ref "D1") (pin "C") (pinfunction "C_C") (pintype "passive"))
      (node (ref "MOS1") (pin "4") (pinfunction "4_4") (pintype "bidirectional"))
      (node (ref "MOS3") (pin "4") (pinfunction "4_4") (pintype "bidirectional"))
      (node (ref "R16") (pin "2") (pinfunction "2_2") (pintype "passive"))
    )
    (net (code "41") (name "Net-(D2-PadC)") (class "Default")
      (node (ref "D2") (pin "C") (pinfunction "C_C") (pintype "passive"))
      (node (ref "MOS2") (pin "4") (pinfunction "4_4") (pintype "bidirectional"))
      (node (ref "MOS6") (pin "4") (pinfunction "4_4") (pintype "bidirectional"))
      (node (ref "R15") (pin "2") (pinfunction "2_2") (pintype "passive"))
    )
    (net (code "42") (name "Net-(D3-PadC)") (class "Default")
      (node (ref "D3") (pin "C") (pinfunction "C_C") (pintype "passive"))
      (node (ref "MOS10") (pin "4") (pinfunction "4_4") (pintype "bidirectional"))
      (node (ref "MOS9") (pin "4") (pinfunction "4_4") (pintype "bidirectional"))
      (node (ref "R18") (pin "2") (pinfunction "2_2") (pintype "passive"))
    )
    (net (code "43") (name "Net-(DCDC1-PadVIN)") (class "Default")
      (node (ref "DCDC1") (pin "VIN") (pinfunction "VIN_VIN") (pintype "bidirectional"))
      (node (ref "MOS1") (pin "1") (pinfunction "1_1") (pintype "bidirectional"))
      (node (ref "MOS1") (pin "2") (pinfunction "2_2") (pintype "bidirectional"))
      (node (ref "MOS1") (pin "5") (pinfunction "5_5") (pintype "bidirectional"))
      (node (ref "MOS1") (pin "6") (pinfunction "6_6") (pintype "bidirectional"))
    )
    (net (code "44") (name "Net-(DCDC2-PadVIN)") (class "Default")
      (node (ref "DCDC2") (pin "VIN") (pinfunction "VIN_VIN") (pintype "bidirectional"))
      (node (ref "MOS2") (pin "1") (pinfunction "1_1") (pintype "bidirectional"))
      (node (ref "MOS2") (pin "2") (pinfunction "2_2") (pintype "bidirectional"))
      (node (ref "MOS2") (pin "5") (pinfunction "5_5") (pintype "bidirectional"))
      (node (ref "MOS2") (pin "6") (pinfunction "6_6") (pintype "bidirectional"))
    )
    (net (code "45") (name "Net-(DCDC3-PadVIN)") (class "Default")
      (node (ref "DCDC3") (pin "VIN") (pinfunction "VIN_VIN") (pintype "bidirectional"))
      (node (ref "MOS10") (pin "1") (pinfunction "1_1") (pintype "bidirectional"))
      (node (ref "MOS10") (pin "2") (pinfunction "2_2") (pintype "bidirectional"))
      (node (ref "MOS10") (pin "5") (pinfunction "5_5") (pintype "bidirectional"))
      (node (ref "MOS10") (pin "6") (pinfunction "6_6") (pintype "bidirectional"))
    )
    (net (code "46") (name "Net-(LED0-PadCT)") (class "Default")
      (node (ref "LED0") (pin "CT") (pinfunction "CT_CT") (pintype "bidirectional"))
      (node (ref "R5") (pin "2") (pinfunction "2_2") (pintype "passive"))
    )
    (net (code "47") (name "Net-(LED1-PadCT)") (class "Default")
      (node (ref "LED1") (pin "CT") (pinfunction "CT_CT") (pintype "bidirectional"))
      (node (ref "R6") (pin "2") (pinfunction "2_2") (pintype "passive"))
    )
    (net (code "48") (name "Net-(LED2-PadCT)") (class "Default")
      (node (ref "LED2") (pin "CT") (pinfunction "CT_CT") (pintype "bidirectional"))
      (node (ref "R22") (pin "2") (pinfunction "2_2") (pintype "passive"))
    )
    (net (code "49") (name "Net-(LED3-PadCT)") (class "Default")
      (node (ref "LED3") (pin "CT") (pinfunction "CT_CT") (pintype "bidirectional"))
      (node (ref "R23") (pin "2") (pinfunction "2_2") (pintype "passive"))
    )
    (net (code "50") (name "Net-(LED4-PadCT)") (class "Default")
      (node (ref "LED4") (pin "CT") (pinfunction "CT_CT") (pintype "bidirectional"))
      (node (ref "R24") (pin "2") (pinfunction "2_2") (pintype "passive"))
    )
    (net (code "51") (name "Net-(LED5-PadCT)") (class "Default")
      (node (ref "LED5") (pin "CT") (pinfunction "CT_CT") (pintype "bidirectional"))
      (node (ref "R28") (pin "2") (pinfunction "2_2") (pintype "passive"))
    )
    (net (code "52") (name "Net-(LED6-PadCT)") (class "Default")
      (node (ref "LED6") (pin "CT") (pinfunction "CT_CT") (pintype "bidirectional"))
      (node (ref "R29") (pin "2") (pinfunction "2_2") (pintype "passive"))
    )
    (net (code "53") (name "Net-(MOS3-Pad1)") (class "Default")
      (node (ref "MOS3") (pin "1") (pinfunction "1_1") (pintype "bidirectional"))
      (node (ref "MOS3") (pin "2") (pinfunction "2_2") (pintype "bidirectional"))
      (node (ref "MOS3") (pin "5") (pinfunction "5_5") (pintype "bidirectional"))
      (node (ref "MOS3") (pin "6") (pinfunction "6_6") (pintype "bidirectional"))
      (node (ref "MOS7") (pin "1") (pinfunction "1_1") (pintype "bidirectional"))
      (node (ref "MOS7") (pin "2") (pinfunction "2_2") (pintype "bidirectional"))
      (node (ref "MOS7") (pin "5") (pinfunction "5_5") (pintype "bidirectional"))
      (node (ref "MOS7") (pin "6") (pinfunction "6_6") (pintype "bidirectional"))
    )
    (net (code "54") (name "Net-(MOS4-Pad1)") (class "Default")
      (node (ref "MOS4") (pin "1") (pinfunction "1_1") (pintype "bidirectional"))
      (node (ref "MOS4") (pin "2") (pinfunction "2_2") (pintype "bidirectional"))
      (node (ref "MOS4") (pin "5") (pinfunction "5_5") (pintype "bidirectional"))
      (node (ref "MOS4") (pin "6") (pinfunction "6_6") (pintype "bidirectional"))
      (node (ref "MOS6") (pin "1") (pinfunction "1_1") (pintype "bidirectional"))
      (node (ref "MOS6") (pin "2") (pinfunction "2_2") (pintype "bidirectional"))
      (node (ref "MOS6") (pin "5") (pinfunction "5_5") (pintype "bidirectional"))
      (node (ref "MOS6") (pin "6") (pinfunction "6_6") (pintype "bidirectional"))
    )
    (net (code "55") (name "Net-(MOS5-Pad1)") (class "Default")
      (node (ref "MOS5") (pin "1") (pinfunction "1_1") (pintype "bidirectional"))
      (node (ref "MOS5") (pin "2") (pinfunction "2_2") (pintype "bidirectional"))
      (node (ref "MOS5") (pin "5") (pinfunction "5_5") (pintype "bidirectional"))
      (node (ref "MOS5") (pin "6") (pinfunction "6_6") (pintype "bidirectional"))
      (node (ref "R13") (pin "1") (pinfunction "1_1") (pintype "passive"))
      (node (ref "R14") (pin "2") (pinfunction "2_2") (pintype "passive"))
    )
    (net (code "56") (name "Net-(MOS8-Pad1)") (class "Default")
      (node (ref "MOS8") (pin "1") (pinfunction "1_1") (pintype "bidirectional"))
      (node (ref "MOS8") (pin "2") (pinfunction "2_2") (pintype "bidirectional"))
      (node (ref "MOS8") (pin "5") (pinfunction "5_5") (pintype "bidirectional"))
      (node (ref "MOS8") (pin "6") (pinfunction "6_6") (pintype "bidirectional"))
      (node (ref "MOS9") (pin "1") (pinfunction "1_1") (pintype "bidirectional"))
      (node (ref "MOS9") (pin "2") (pinfunction "2_2") (pintype "bidirectional"))
      (node (ref "MOS9") (pin "5") (pinfunction "5_5") (pintype "bidirectional"))
      (node (ref "MOS9") (pin "6") (pinfunction "6_6") (pintype "bidirectional"))
    )
    (net (code "57") (name "Net-(PWR-PadCT)") (class "Default")
      (node (ref "PWR") (pin "CT") (pinfunction "CT_CT") (pintype "bidirectional"))
      (node (ref "R3") (pin "2") (pinfunction "2_2") (pintype "passive"))
    )
    (net (code "58") (name "Net-(PWR1-PadCT)") (class "Default")
      (node (ref "PWR1") (pin "CT") (pinfunction "CT_CT") (pintype "bidirectional"))
      (node (ref "R21") (pin "2") (pinfunction "2_2") (pintype "passive"))
    )
    (net (code "59") (name "Net-(PWR2-PadCT)") (class "Default")
      (node (ref "PWR2") (pin "CT") (pinfunction "CT_CT") (pintype "bidirectional"))
      (node (ref "R27") (pin "2") (pinfunction "2_2") (pintype "passive"))
    )
    (net (code "60") (name "OSC_IN1") (class "Default")
      (node (ref "STM1") (pin "PF0") (pinfunction "PF0_PF0") (pintype "bidirectional"))
    )
    (net (code "61") (name "OSC_IN2") (class "Default")
      (node (ref "U$1") (pin "PF0") (pinfunction "PF0_PF0") (pintype "bidirectional"))
    )
    (net (code "62") (name "OSC_OUT1") (class "Default")
      (node (ref "STM1") (pin "PF1") (pinfunction "PF1_PF1") (pintype "bidirectional"))
    )
    (net (code "63") (name "OSC_OUT2") (class "Default")
      (node (ref "U$1") (pin "PF1") (pinfunction "PF1_PF1") (pintype "bidirectional"))
    )
    (net (code "64") (name "PWM") (class "Default")
      (node (ref "SV") (pin "P$1") (pinfunction "P$1_P$1") (pintype "bidirectional"))
      (node (ref "U$1") (pin "PA5/SPI1_SCK") (pinfunction "PA5/SPI1_SCK_PA5/SPI1_SCK") (pintype "bidirectional"))
    )
    (net (code "65") (name "RXCAN") (class "Default")
      (node (ref "STM0") (pin "PA12/CAN_TX") (pinfunction "PA12/CAN_TX_PA12/CAN_TX") (pintype "bidirectional"))
      (node (ref "U$3") (pin "4") (pinfunction "RXD_4") (pintype "output"))
    )
    (net (code "66") (name "RXCAN1") (class "Default")
      (node (ref "STM1") (pin "PA12/CAN_TX") (pinfunction "PA12/CAN_TX_PA12/CAN_TX") (pintype "bidirectional"))
      (node (ref "U$5") (pin "4") (pinfunction "RXD_4") (pintype "output"))
    )
    (net (code "67") (name "RXCAN2") (class "Default")
      (node (ref "U$1") (pin "PA12/CAN_TX") (pinfunction "PA12/CAN_TX_PA12/CAN_TX") (pintype "bidirectional"))
      (node (ref "U$6") (pin "4") (pinfunction "RXD_4") (pintype "output"))
    )
    (net (code "68") (name "SCK") (class "Default")
      (node (ref "R11") (pin "1") (pinfunction "1_1") (pintype "passive"))
      (node (ref "STM0") (pin "PA5/SPI1_SCK") (pinfunction "PA5/SPI1_SCK_PA5/SPI1_SCK") (pintype "bidirectional"))
    )
    (net (code "69") (name "SCL0") (class "Default")
      (node (ref "BMP1") (pin "P3") (pinfunction "SCL_P3") (pintype "bidirectional"))
      (node (ref "BMX1") (pin "SCL") (pinfunction "SCL_SCL") (pintype "bidirectional"))
      (node (ref "R33") (pin "2") (pinfunction "2_2") (pintype "passive"))
      (node (ref "STM0") (pin "PA15/I2C1_SCL") (pinfunction "PA15/I2C1_SCL_PA15/I2C1_SCL") (pintype "bidirectional"))
    )
    (net (code "70") (name "SCL1") (class "Default")
      (node (ref "BMP3") (pin "P3") (pinfunction "SCL_P3") (pintype "bidirectional"))
      (node (ref "R35") (pin "2") (pinfunction "2_2") (pintype "passive"))
      (node (ref "STM1") (pin "PA15/I2C1_SCL") (pinfunction "PA15/I2C1_SCL_PA15/I2C1_SCL") (pintype "bidirectional"))
    )
    (net (code "71") (name "SCL2") (class "Default")
      (node (ref "BMP2") (pin "P3") (pinfunction "SCL_P3") (pintype "bidirectional"))
      (node (ref "BMX2") (pin "SCL") (pinfunction "SCL_SCL") (pintype "bidirectional"))
      (node (ref "R31") (pin "2") (pinfunction "2_2") (pintype "passive"))
      (node (ref "U$1") (pin "PA15/I2C1_SCL") (pinfunction "PA15/I2C1_SCL_PA15/I2C1_SCL") (pintype "bidirectional"))
    )
    (net (code "72") (name "SDA0") (class "Default")
      (node (ref "BMP1") (pin "P4") (pinfunction "SDA_P4") (pintype "bidirectional"))
      (node (ref "BMX1") (pin "SDA") (pinfunction "SDA_SDA") (pintype "bidirectional"))
      (node (ref "R32") (pin "1") (pinfunction "1_1") (pintype "passive"))
      (node (ref "STM0") (pin "PB7/I2C1_SDA") (pinfunction "PB7/I2C1_SDA_PB7/I2C1_SDA") (pintype "bidirectional"))
    )
    (net (code "73") (name "SDA1") (class "Default")
      (node (ref "BMP3") (pin "P4") (pinfunction "SDA_P4") (pintype "bidirectional"))
      (node (ref "R34") (pin "1") (pinfunction "1_1") (pintype "passive"))
      (node (ref "STM1") (pin "PB7/I2C1_SDA") (pinfunction "PB7/I2C1_SDA_PB7/I2C1_SDA") (pintype "bidirectional"))
    )
    (net (code "74") (name "SDA2") (class "Default")
      (node (ref "BMP2") (pin "P4") (pinfunction "SDA_P4") (pintype "bidirectional"))
      (node (ref "BMX2") (pin "SDA") (pinfunction "SDA_SDA") (pintype "bidirectional"))
      (node (ref "R30") (pin "1") (pinfunction "1_1") (pintype "passive"))
      (node (ref "U$1") (pin "PB7/I2C1_SDA") (pinfunction "PB7/I2C1_SDA_PB7/I2C1_SDA") (pintype "bidirectional"))
    )
    (net (code "75") (name "SW") (class "Default")
      (node (ref "MOS1") (pin "3") (pinfunction "3_3") (pintype "bidirectional"))
      (node (ref "MOS10") (pin "3") (pinfunction "3_3") (pintype "bidirectional"))
      (node (ref "MOS2") (pin "3") (pinfunction "3_3") (pintype "bidirectional"))
      (node (ref "R15") (pin "1") (pinfunction "1_1") (pintype "passive"))
      (node (ref "R16") (pin "1") (pinfunction "1_1") (pintype "passive"))
      (node (ref "R18") (pin "1") (pinfunction "1_1") (pintype "passive"))
      (node (ref "SW1") (pin "L") (pinfunction "L_L") (pintype "bidirectional"))
    )
    (net (code "76") (name "SWCLK") (class "Default")
      (node (ref "JP1") (pin "3") (pinfunction "3_3") (pintype "passive"))
      (node (ref "STM0") (pin "PA14/SWCLK") (pinfunction "PA14/SWCLK_PA14/SWCLK") (pintype "bidirectional"))
    )
    (net (code "77") (name "SWCLK1") (class "Default")
      (node (ref "JP3") (pin "3") (pinfunction "3_3") (pintype "passive"))
      (node (ref "STM1") (pin "PA14/SWCLK") (pinfunction "PA14/SWCLK_PA14/SWCLK") (pintype "bidirectional"))
    )
    (net (code "78") (name "SWCLK2") (class "Default")
      (node (ref "JP4") (pin "3") (pinfunction "3_3") (pintype "passive"))
      (node (ref "U$1") (pin "PA14/SWCLK") (pinfunction "PA14/SWCLK_PA14/SWCLK") (pintype "bidirectional"))
    )
    (net (code "79") (name "SWDIO") (class "Default")
      (node (ref "JP1") (pin "1") (pinfunction "1_1") (pintype "passive"))
      (node (ref "STM0") (pin "PA13/SWDIO") (pinfunction "PA13/SWDIO_PA13/SWDIO") (pintype "bidirectional"))
    )
    (net (code "80") (name "SWDIO1") (class "Default")
      (node (ref "JP3") (pin "1") (pinfunction "1_1") (pintype "passive"))
      (node (ref "STM1") (pin "PA13/SWDIO") (pinfunction "PA13/SWDIO_PA13/SWDIO") (pintype "bidirectional"))
    )
    (net (code "81") (name "SWDIO2") (class "Default")
      (node (ref "JP4") (pin "5") (pinfunction "5_5") (pintype "passive"))
      (node (ref "U$1") (pin "PA13/SWDIO") (pinfunction "PA13/SWDIO_PA13/SWDIO") (pintype "bidirectional"))
    )
    (net (code "82") (name "SWO") (class "Default")
      (node (ref "JP1") (pin "5") (pinfunction "5_5") (pintype "passive"))
      (node (ref "STM0") (pin "PB3/SWO") (pinfunction "PB3/TRACESWO_PB3/SWO") (pintype "bidirectional"))
    )
    (net (code "83") (name "SWO1") (class "Default")
      (node (ref "JP3") (pin "5") (pinfunction "5_5") (pintype "passive"))
      (node (ref "STM1") (pin "PB3/SWO") (pinfunction "PB3/TRACESWO_PB3/SWO") (pintype "bidirectional"))
    )
    (net (code "84") (name "SWO2") (class "Default")
      (node (ref "JP4") (pin "1") (pinfunction "1_1") (pintype "passive"))
      (node (ref "U$1") (pin "PB3/SWO") (pinfunction "PB3/TRACESWO_PB3/SWO") (pintype "bidirectional"))
    )
    (net (code "85") (name "TXCAN") (class "Default")
      (node (ref "STM0") (pin "PA11/CAN_RX") (pinfunction "PA11/CAN_RX_PA11/CAN_RX") (pintype "bidirectional"))
      (node (ref "U$3") (pin "1") (pinfunction "TXD_1") (pintype "input"))
    )
    (net (code "86") (name "TXCAN1") (class "Default")
      (node (ref "STM1") (pin "PA11/CAN_RX") (pinfunction "PA11/CAN_RX_PA11/CAN_RX") (pintype "bidirectional"))
      (node (ref "U$5") (pin "1") (pinfunction "TXD_1") (pintype "input"))
    )
    (net (code "87") (name "TXCAN2") (class "Default")
      (node (ref "U$1") (pin "PA11/CAN_RX") (pinfunction "PA11/CAN_RX_PA11/CAN_RX") (pintype "bidirectional"))
      (node (ref "U$6") (pin "1") (pinfunction "TXD_1") (pintype "input"))
    )
    (net (code "88") (name "unconnected-(CN1-PadDAT1)") (class "Default")
      (node (ref "CN1") (pin "DAT1") (pinfunction "DAT1_DAT1") (pintype "bidirectional"))
    )
    (net (code "89") (name "unconnected-(CN1-PadDAT2)") (class "Default")
      (node (ref "CN1") (pin "DAT2") (pinfunction "DAT2_DAT2") (pintype "bidirectional"))
    )
    (net (code "90") (name "unconnected-(CN1-PadDET_A)") (class "Default")
      (node (ref "CN1") (pin "DET_A") (pinfunction "DET_A_DET_A") (pintype "bidirectional"))
    )
    (net (code "91") (name "unconnected-(CN1-PadDET_B)") (class "Default")
      (node (ref "CN1") (pin "DET_B") (pinfunction "DET_B_DET_B") (pintype "bidirectional"))
    )
    (net (code "92") (name "unconnected-(IM1-IO2-Pad$P2)") (class "Default")
      (node (ref "IM1") (pin "$P2") (pinfunction "IO2_$P2") (pintype "bidirectional"))
    )
    (net (code "93") (name "unconnected-(IM1-IO5-Pad$P5)") (class "Default")
      (node (ref "IM1") (pin "$P5") (pinfunction "IO5_$P5") (pintype "bidirectional"))
    )
    (net (code "94") (name "unconnected-(IM1-IO8-Pad$P8)") (class "Default")
      (node (ref "IM1") (pin "$P8") (pinfunction "IO8_$P8") (pintype "bidirectional"))
    )
    (net (code "95") (name "unconnected-(IM1-MODE1{slash}IO9-Pad$P9)") (class "Default")
      (node (ref "IM1") (pin "$P9") (pinfunction "MODE1/IO9_$P9") (pintype "bidirectional"))
    )
    (net (code "96") (name "unconnected-(IM1-MODE2{slash}IO10-Pad$P10)") (class "Default")
      (node (ref "IM1") (pin "$P10") (pinfunction "MODE2/IO10_$P10") (pintype "bidirectional"))
    )
    (net (code "97") (name "unconnected-(IM1-REG-Pad$P16)") (class "Default")
      (node (ref "IM1") (pin "$P16") (pinfunction "REG_$P16") (pintype "bidirectional"))
    )
    (net (code "98") (name "unconnected-(IM1-SLEEP{slash}IO4-Pad$P4)") (class "Default")
      (node (ref "IM1") (pin "$P4") (pinfunction "SLEEP/IO4_$P4") (pintype "bidirectional"))
    )
    (net (code "99") (name "unconnected-(IM1-XMIT{slash}IO3-Pad$P3)") (class "Default")
      (node (ref "IM1") (pin "$P3") (pinfunction "XMIT/IO3_$P3") (pintype "bidirectional"))
    )
    (net (code "100") (name "unconnected-(JP1-Pad4)") (class "Default")
      (node (ref "JP1") (pin "4") (pinfunction "4_4") (pintype "passive"))
    )
    (net (code "101") (name "unconnected-(JP3-Pad4)") (class "Default")
      (node (ref "JP3") (pin "4") (pinfunction "4_4") (pintype "passive"))
    )
    (net (code "102") (name "unconnected-(JP4-Pad4)") (class "Default")
      (node (ref "JP4") (pin "4") (pinfunction "4_4") (pintype "passive"))
    )
    (net (code "103") (name "unconnected-(STM0-PadPA0)") (class "Default")
      (node (ref "STM0") (pin "PA0") (pinfunction "PA0_PA0") (pintype "bidirectional"))
    )
    (net (code "104") (name "unconnected-(STM0-PadPA1)") (class "Default")
      (node (ref "STM0") (pin "PA1") (pinfunction "PA1_PA1") (pintype "bidirectional"))
    )
    (net (code "105") (name "unconnected-(STM0-PadPA2{slash}UART2_TX)") (class "Default")
      (node (ref "STM0") (pin "PA2/UART2_TX") (pinfunction "PA2/UART2_TX_PA2/UART2_TX") (pintype "bidirectional"))
    )
    (net (code "106") (name "unconnected-(STM0-PadPA3{slash}UART2_RX)") (class "Default")
      (node (ref "STM0") (pin "PA3/UART2_RX") (pinfunction "PA3/UART2_RX_PA3/UART2_RX") (pintype "bidirectional"))
    )
    (net (code "107") (name "unconnected-(STM0-PadPA8)") (class "Default")
      (node (ref "STM0") (pin "PA8") (pinfunction "PA8_PA8") (pintype "bidirectional"))
    )
    (net (code "108") (name "unconnected-(STM0-PadPB5)") (class "Default")
      (node (ref "STM0") (pin "PB5") (pinfunction "PB5_PB5") (pintype "bidirectional"))
    )
    (net (code "109") (name "unconnected-(STM0-PadPB6)") (class "Default")
      (node (ref "STM0") (pin "PB6") (pinfunction "PB6_PB6") (pintype "bidirectional"))
    )
    (net (code "110") (name "unconnected-(STM0-PadPF0)") (class "Default")
      (node (ref "STM0") (pin "PF0") (pinfunction "PF0_PF0") (pintype "bidirectional"))
    )
    (net (code "111") (name "unconnected-(STM0-PadPF1)") (class "Default")
      (node (ref "STM0") (pin "PF1") (pinfunction "PF1_PF1") (pintype "bidirectional"))
    )
    (net (code "112") (name "unconnected-(STM1-PadPA0)") (class "Default")
      (node (ref "STM1") (pin "PA0") (pinfunction "PA0_PA0") (pintype "bidirectional"))
    )
    (net (code "113") (name "unconnected-(STM1-PadPA1)") (class "Default")
      (node (ref "STM1") (pin "PA1") (pinfunction "PA1_PA1") (pintype "bidirectional"))
    )
    (net (code "114") (name "unconnected-(STM1-PadPA4{slash}SPI1_NSS)") (class "Default")
      (node (ref "STM1") (pin "PA4/SPI1_NSS") (pinfunction "PA4/SPI1_NSS_PA4/SPI1_NSS") (pintype "bidirectional"))
    )
    (net (code "115") (name "unconnected-(STM1-PadPA7{slash}SPI1_MOSI)") (class "Default")
      (node (ref "STM1") (pin "PA7/SPI1_MOSI") (pinfunction "PA7/SPI1_MOSI_PA7/SPI1_MOSI") (pintype "bidirectional"))
    )
    (net (code "116") (name "unconnected-(STM1-PadPA8)") (class "Default")
      (node (ref "STM1") (pin "PA8") (pinfunction "PA8_PA8") (pintype "bidirectional"))
    )
    (net (code "117") (name "unconnected-(STM1-PadPB5)") (class "Default")
      (node (ref "STM1") (pin "PB5") (pinfunction "PB5_PB5") (pintype "bidirectional"))
    )
    (net (code "118") (name "unconnected-(STM1-PadPB6)") (class "Default")
      (node (ref "STM1") (pin "PB6") (pinfunction "PB6_PB6") (pintype "bidirectional"))
    )
    (net (code "119") (name "unconnected-(SW1-PadR)") (class "Default")
      (node (ref "SW1") (pin "R") (pinfunction "R_R") (pintype "bidirectional"))
    )
    (net (code "120") (name "unconnected-(U$1-PadPA0)") (class "Default")
      (node (ref "U$1") (pin "PA0") (pinfunction "PA0_PA0") (pintype "bidirectional"))
    )
    (net (code "121") (name "unconnected-(U$1-PadPA1)") (class "Default")
      (node (ref "U$1") (pin "PA1") (pinfunction "PA1_PA1") (pintype "bidirectional"))
    )
    (net (code "122") (name "unconnected-(U$1-PadPA2{slash}UART2_TX)") (class "Default")
      (node (ref "U$1") (pin "PA2/UART2_TX") (pinfunction "PA2/UART2_TX_PA2/UART2_TX") (pintype "bidirectional"))
    )
    (net (code "123") (name "unconnected-(U$1-PadPA3{slash}UART2_RX)") (class "Default")
      (node (ref "U$1") (pin "PA3/UART2_RX") (pinfunction "PA3/UART2_RX_PA3/UART2_RX") (pintype "bidirectional"))
    )
    (net (code "124") (name "unconnected-(U$1-PadPA4{slash}SPI1_NSS)") (class "Default")
      (node (ref "U$1") (pin "PA4/SPI1_NSS") (pinfunction "PA4/SPI1_NSS_PA4/SPI1_NSS") (pintype "bidirectional"))
    )
    (net (code "125") (name "unconnected-(U$1-PadPA6{slash}SPI1_MISO)") (class "Default")
      (node (ref "U$1") (pin "PA6/SPI1_MISO") (pinfunction "PA6/SPI1_MISO_PA6/SPI1_MISO") (pintype "bidirectional"))
    )
    (net (code "126") (name "unconnected-(U$1-PadPA7{slash}SPI1_MOSI)") (class "Default")
      (node (ref "U$1") (pin "PA7/SPI1_MOSI") (pinfunction "PA7/SPI1_MOSI_PA7/SPI1_MOSI") (pintype "bidirectional"))
    )
    (net (code "127") (name "unconnected-(U$1-PadPA8)") (class "Default")
      (node (ref "U$1") (pin "PA8") (pinfunction "PA8_PA8") (pintype "bidirectional"))
    )
    (net (code "128") (name "unconnected-(U$1-PadPB5)") (class "Default")
      (node (ref "U$1") (pin "PB5") (pinfunction "PB5_PB5") (pintype "bidirectional"))
    )
    (net (code "129") (name "unconnected-(U$1-PadPB6)") (class "Default")
      (node (ref "U$1") (pin "PB6") (pinfunction "PB6_PB6") (pintype "bidirectional"))
    )
    (net (code "130") (name "unconnected-(U$2-1PPS-PadP5)") (class "Default")
      (node (ref "U$2") (pin "P5") (pinfunction "1PPS_P5") (pintype "bidirectional"))
    )
  )
)
